# OpenBook.net
KiCad netlist of a schematic drawn in EAGLE
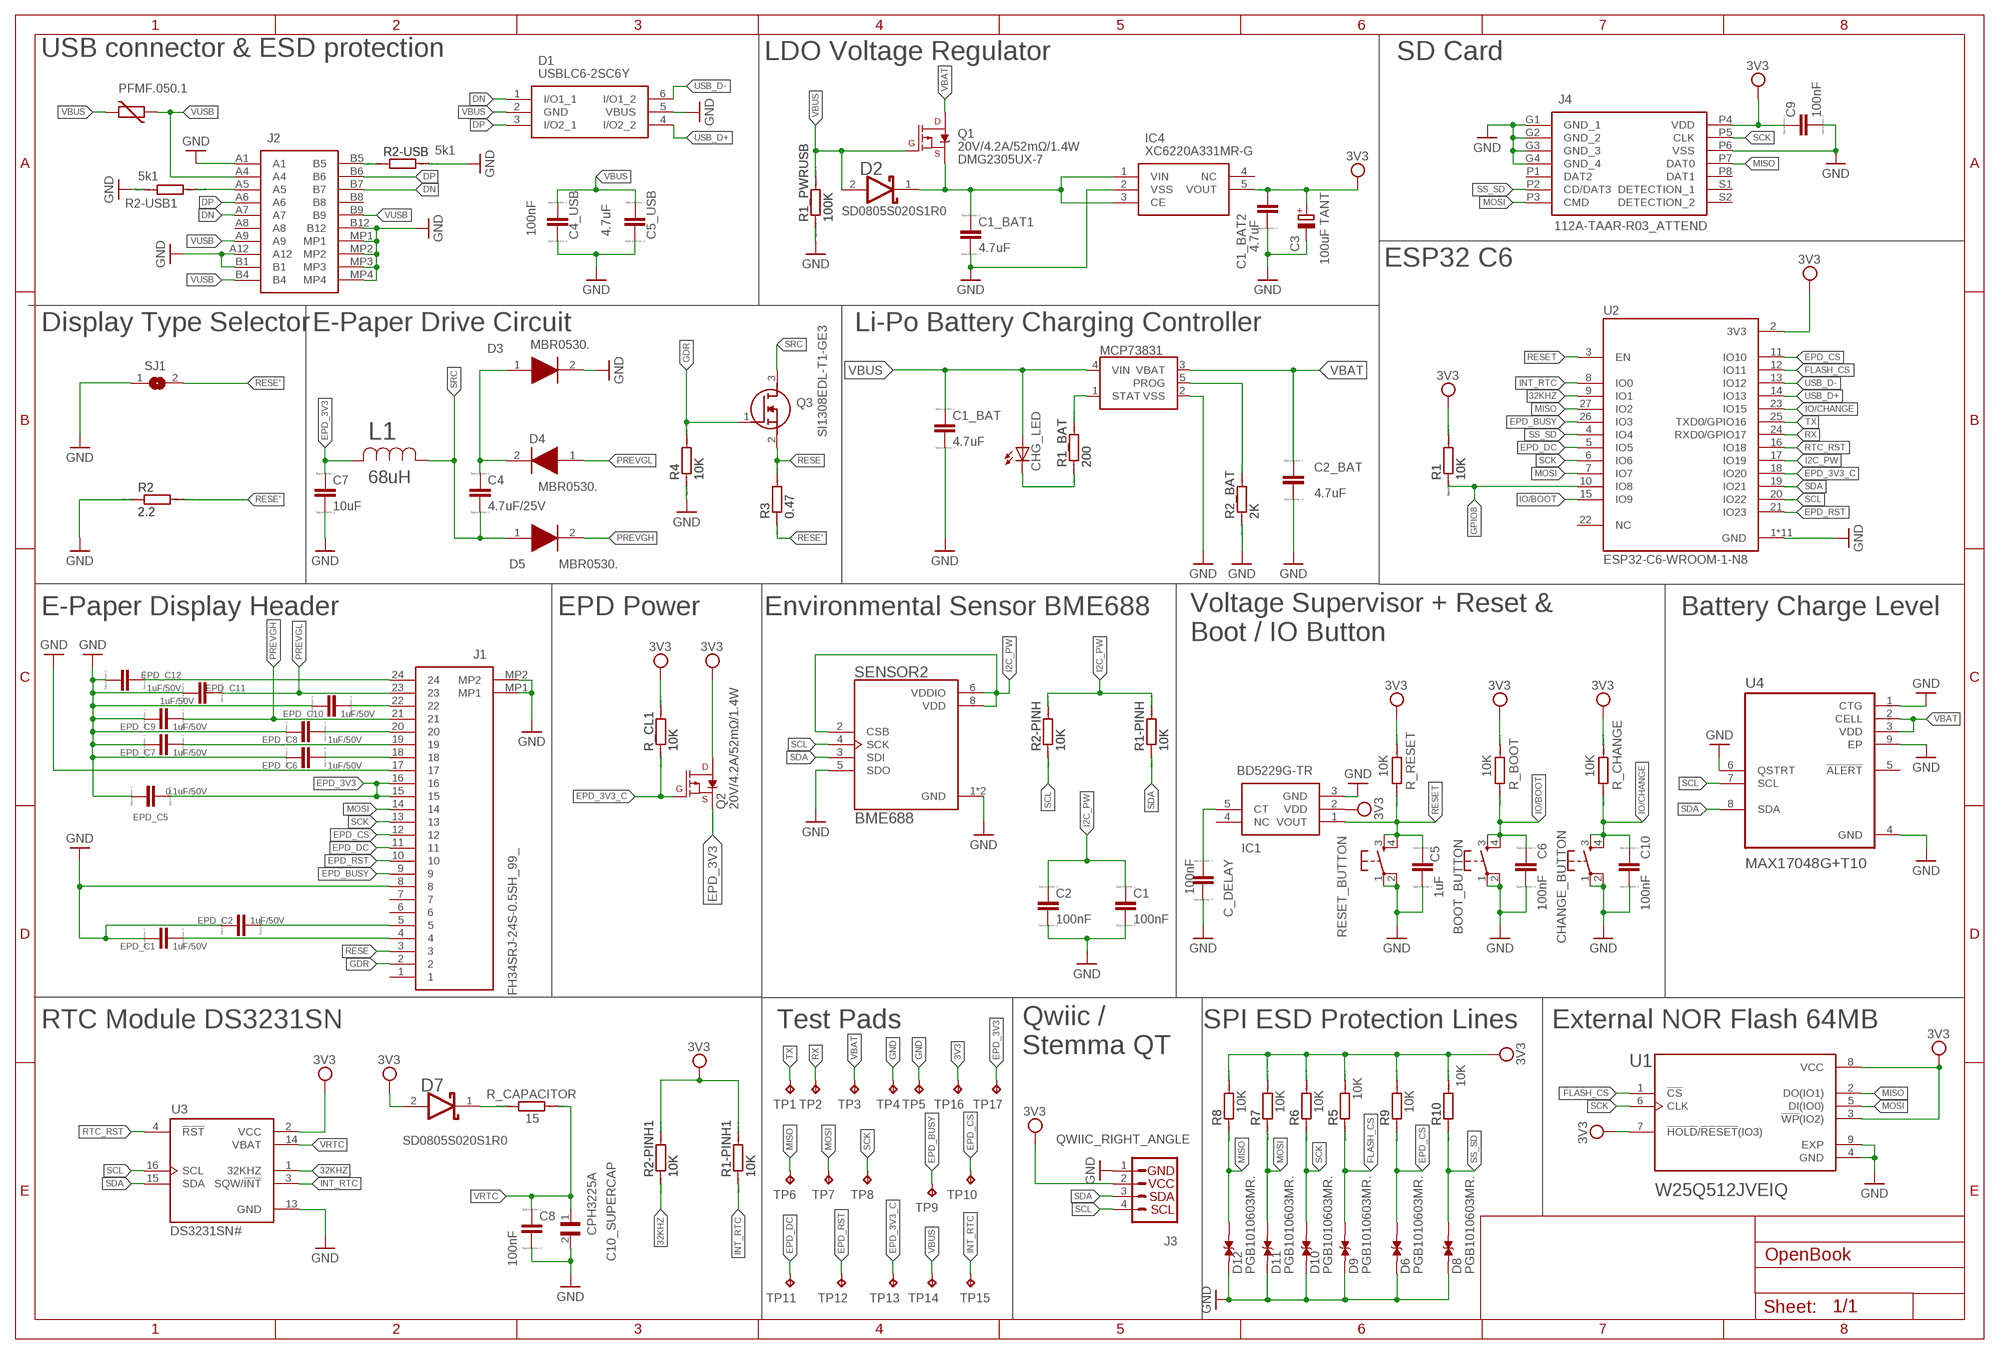
[diagram p0: schematic, sheet 1]

(export (version "E")
  (design (tool "Eeschema 10.0.6"))
  (components
    (comp (ref "BOOT_BUTTON")
      (value "BUTTON_CUSYOMV1V2")
      (footprint "eagle-import:MYBUTTON")
      (libsource (lib "eagle-import") (part "BUTTON_CUSYOMV1V2"))
    )
    (comp (ref "C1")
      (value "100nF")
      (footprint "eagle-import:EAGLE-LTSPICE_C0402")
      (libsource (lib "eagle-import") (part "EAGLE-LTSPICE_C"))
    )
    (comp (ref "C1_BAT")
      (value "4.7uF")
      (footprint "eagle-import:EAGLE-LTSPICE_C0402")
      (libsource (lib "eagle-import") (part "EAGLE-LTSPICE_C"))
    )
    (comp (ref "C1_BAT1")
      (value "4.7uF")
      (footprint "eagle-import:EAGLE-LTSPICE_C0402")
      (libsource (lib "eagle-import") (part "EAGLE-LTSPICE_C"))
    )
    (comp (ref "C1_BAT2")
      (value "4.7uF")
      (footprint "eagle-import:EAGLE-LTSPICE_C0402")
      (libsource (lib "eagle-import") (part "EAGLE-LTSPICE_C"))
    )
    (comp (ref "C2")
      (value "100nF")
      (footprint "eagle-import:EAGLE-LTSPICE_C0402")
      (libsource (lib "eagle-import") (part "EAGLE-LTSPICE_C"))
    )
    (comp (ref "C2_BAT")
      (value "4.7uF")
      (footprint "eagle-import:EAGLE-LTSPICE_C0402")
      (libsource (lib "eagle-import") (part "EAGLE-LTSPICE_C"))
    )
    (comp (ref "C3")
      (value "100uF TANT")
      (footprint "eagle-import:RCL_CT3528")
      (libsource (lib "eagle-import") (part "RCL_CPOL-EUCT3528"))
    )
    (comp (ref "C4")
      (value "4.7uF/25V")
      (footprint "eagle-import:EAGLE-LTSPICE_C0402")
      (libsource (lib "eagle-import") (part "EAGLE-LTSPICE_C"))
    )
    (comp (ref "C4_USB")
      (value "100nF")
      (footprint "eagle-import:EAGLE-LTSPICE_C0402")
      (libsource (lib "eagle-import") (part "EAGLE-LTSPICE_C"))
    )
    (comp (ref "C5")
      (value "1uF")
      (footprint "eagle-import:EAGLE-LTSPICE_C0402")
      (libsource (lib "eagle-import") (part "EAGLE-LTSPICE_C"))
    )
    (comp (ref "C5_USB")
      (value "4.7uF")
      (footprint "eagle-import:EAGLE-LTSPICE_C0402")
      (libsource (lib "eagle-import") (part "EAGLE-LTSPICE_C"))
    )
    (comp (ref "C6")
      (value "100nF")
      (footprint "eagle-import:EAGLE-LTSPICE_C0402")
      (libsource (lib "eagle-import") (part "EAGLE-LTSPICE_C"))
    )
    (comp (ref "C7")
      (value "10uF")
      (footprint "eagle-import:EAGLE-LTSPICE_C0402")
      (libsource (lib "eagle-import") (part "EAGLE-LTSPICE_C"))
    )
    (comp (ref "C8")
      (value "100nF")
      (footprint "eagle-import:EAGLE-LTSPICE_C0402")
      (libsource (lib "eagle-import") (part "EAGLE-LTSPICE_C"))
    )
    (comp (ref "C9")
      (value "100nF")
      (footprint "eagle-import:EAGLE-LTSPICE_C0402")
      (libsource (lib "eagle-import") (part "EAGLE-LTSPICE_C"))
    )
    (comp (ref "C10")
      (value "100nF")
      (footprint "eagle-import:EAGLE-LTSPICE_C0402")
      (libsource (lib "eagle-import") (part "EAGLE-LTSPICE_C"))
    )
    (comp (ref "C10_SUPERCAP")
      (value "CPH3225A")
      (footprint "eagle-import:CAPCP3225X100N")
      (fields (field (name "MF") "Seiko Instruments"))
      (libsource (lib "eagle-import") (part "CPH3225A"))
    )
    (comp (ref "CHANGE_BUTTON")
      (value "BUTTON_CUSYOMV1V2")
      (footprint "eagle-import:MYBUTTON")
      (libsource (lib "eagle-import") (part "BUTTON_CUSYOMV1V2"))
    )
    (comp (ref "CHG_LED")
      (value "ADAFRUIT_LEDCHIP-LED0603")
      (footprint "eagle-import:ADAFRUIT_CHIP-LED0603")
      (libsource (lib "eagle-import") (part "ADAFRUIT_LEDCHIP-LED0603"))
    )
    (comp (ref "C_DELAY")
      (value "100nF")
      (footprint "eagle-import:EAGLE-LTSPICE_C0402")
      (libsource (lib "eagle-import") (part "EAGLE-LTSPICE_C"))
    )
    (comp (ref "D1")
      (value "USBLC6-2SC6Y")
      (footprint "eagle-import:SOT95P280X145-6N")
      (fields (field (name "MF") "STMicroelectronics"))
      (libsource (lib "eagle-import") (part "USBLC6-2SC6Y"))
    )
    (comp (ref "D2")
      (value "SD0805S020S1R0")
      (footprint "eagle-import:ESP32_WROVER_AVX---SD0805S020S1R0_AVX_SD0805S020S1R0_0")
      (fields
        (field (name "DIGIKEY_PART_NUMBER") "478-7800-1-ND")
        (field (name "MF") "AVX")
        (field (name "MOUSER_PART_NUMBER") "581-SD0805S020S1R0")
      )
      (libsource (lib "eagle-import") (part "ESP32_WROVER_AVX---SD0805S020S1R0_AVX_SD0805S020S1R0_0_0AVX_SD0805S020S1R0_0_0"))
    )
    (comp (ref "D3")
      (value "MBR0530.")
      (footprint "eagle-import:SOD3716X135N")
      (libsource (lib "eagle-import") (part "MBR0530."))
    )
    (comp (ref "D4")
      (value "MBR0530.")
      (footprint "eagle-import:SOD3716X135N")
      (libsource (lib "eagle-import") (part "MBR0530."))
    )
    (comp (ref "D5")
      (value "MBR0530.")
      (footprint "eagle-import:SOD3716X135N")
      (libsource (lib "eagle-import") (part "MBR0530."))
    )
    (comp (ref "D6")
      (value "PGB1010603MR.")
      (footprint "eagle-import:DIOC1608X36N")
      (libsource (lib "eagle-import") (part "PGB1010603MR."))
    )
    (comp (ref "D7")
      (value "SD0805S020S1R0")
      (footprint "eagle-import:ESP32_WROVER_AVX---SD0805S020S1R0_AVX_SD0805S020S1R0_0")
      (fields
        (field (name "DIGIKEY_PART_NUMBER") "478-7800-1-ND")
        (field (name "MF") "AVX")
        (field (name "MOUSER_PART_NUMBER") "581-SD0805S020S1R0")
      )
      (libsource (lib "eagle-import") (part "ESP32_WROVER_AVX---SD0805S020S1R0_AVX_SD0805S020S1R0_0_0AVX_SD0805S020S1R0_0_0"))
    )
    (comp (ref "D8")
      (value "PGB1010603MR.")
      (footprint "eagle-import:DIOC1608X36N")
      (libsource (lib "eagle-import") (part "PGB1010603MR."))
    )
    (comp (ref "D9")
      (value "PGB1010603MR.")
      (footprint "eagle-import:DIOC1608X36N")
      (libsource (lib "eagle-import") (part "PGB1010603MR."))
    )
    (comp (ref "D10")
      (value "PGB1010603MR.")
      (footprint "eagle-import:DIOC1608X36N")
      (libsource (lib "eagle-import") (part "PGB1010603MR."))
    )
    (comp (ref "D11")
      (value "PGB1010603MR.")
      (footprint "eagle-import:DIOC1608X36N")
      (libsource (lib "eagle-import") (part "PGB1010603MR."))
    )
    (comp (ref "D12")
      (value "PGB1010603MR.")
      (footprint "eagle-import:DIOC1608X36N")
      (libsource (lib "eagle-import") (part "PGB1010603MR."))
    )
    (comp (ref "EPD_C1")
      (value "1uF/50V")
      (footprint "eagle-import:EAGLE-LTSPICE_C0402")
      (libsource (lib "eagle-import") (part "EAGLE-LTSPICE_C"))
    )
    (comp (ref "EPD_C2")
      (value "1uF/50V")
      (footprint "eagle-import:EAGLE-LTSPICE_C0402")
      (libsource (lib "eagle-import") (part "EAGLE-LTSPICE_C"))
    )
    (comp (ref "EPD_C5")
      (value "0.1uF/50V")
      (footprint "eagle-import:EAGLE-LTSPICE_C0402")
      (libsource (lib "eagle-import") (part "EAGLE-LTSPICE_C"))
    )
    (comp (ref "EPD_C6")
      (value "1uF/50V")
      (footprint "eagle-import:EAGLE-LTSPICE_C0402")
      (libsource (lib "eagle-import") (part "EAGLE-LTSPICE_C"))
    )
    (comp (ref "EPD_C7")
      (value "1uF/50V")
      (footprint "eagle-import:EAGLE-LTSPICE_C0402")
      (libsource (lib "eagle-import") (part "EAGLE-LTSPICE_C"))
    )
    (comp (ref "EPD_C8")
      (value "1uF/50V")
      (footprint "eagle-import:EAGLE-LTSPICE_C0402")
      (libsource (lib "eagle-import") (part "EAGLE-LTSPICE_C"))
    )
    (comp (ref "EPD_C9")
      (value "1uF/50V")
      (footprint "eagle-import:EAGLE-LTSPICE_C0402")
      (libsource (lib "eagle-import") (part "EAGLE-LTSPICE_C"))
    )
    (comp (ref "EPD_C10")
      (value "1uF/50V")
      (footprint "eagle-import:EAGLE-LTSPICE_C0402")
      (libsource (lib "eagle-import") (part "EAGLE-LTSPICE_C"))
    )
    (comp (ref "EPD_C11")
      (value "1uF/50V")
      (footprint "eagle-import:EAGLE-LTSPICE_C0402")
      (libsource (lib "eagle-import") (part "EAGLE-LTSPICE_C"))
    )
    (comp (ref "EPD_C12")
      (value "1uF/50V")
      (footprint "eagle-import:EAGLE-LTSPICE_C0402")
      (libsource (lib "eagle-import") (part "EAGLE-LTSPICE_C"))
    )
    (comp (ref "IC1")
      (value "BD5229G-TR")
      (footprint "eagle-import:SOT95P280X125-5N")
      (fields (field (name "MOUSER_PART_NUMBER") "755-BD5229G-TR"))
      (libsource (lib "eagle-import") (part "BD5229G-TR"))
    )
    (comp (ref "IC4")
      (value "XC6220A331MR-G")
      (footprint "eagle-import:SOT95P280X120-5N")
      (fields (field (name "MOUSER_PART_NUMBER") "865-XC6220A331MR-G"))
      (libsource (lib "eagle-import") (part "XC6220A331MR-G"))
    )
    (comp (ref "J1")
      (value "FH34SRJ-24S-0.5SH_99_")
      (footprint "eagle-import:FH34SRJ24S05SH99")
      (fields
        (field (name "MANUFACTURER_PART_NUMBER") "FH34SRJ-24S-0.5SH(99)")
        (field (name "MOUSER_PART_NUMBER") "798-FH34SRJ24S05SH99")
      )
      (libsource (lib "eagle-import") (part "FH34SRJ-24S-0.5SH_99_"))
    )
    (comp (ref "J2")
      (value "SAMACSYS_PARTS_USB4110-GF-A")
      (footprint "eagle-import:SAMACSYS_PARTS_USB4110GFA")
      (fields
        (field (name "MANUFACTURER_PART_NUMBER") "USB4110-GF-A")
        (field (name "MOUSER_PART_NUMBER") "640-USB4110-GF-A")
      )
      (libsource (lib "eagle-import") (part "SAMACSYS_PARTS_USB4110-GF-A"))
    )
    (comp (ref "J3")
      (value "QWIIC_RIGHT_ANGLE")
      (footprint "eagle-import:JST04_1MM_RA")
      (libsource (lib "eagle-import") (part "QWIIC_CONNECTORJS-1MM"))
    )
    (comp (ref "J4")
      (value "112A-TAAR-R03_ATTEND")
      (footprint "eagle-import:112ATAARR03ATTEND")
      (fields (field (name "MANUFACTURER_PART_NUMBER") "112A-TAAR-R03 ATTEND"))
      (libsource (lib "eagle-import") (part "112A-TAAR-R03_ATTEND"))
    )
    (comp (ref "L1")
      (value "68uH")
      (footprint "eagle-import:IND_4828-WE-TPC_WRE")
      (fields
        (field (name "MANUFACTURER_PART_NUMBER") "744043680")
        (field (name "COPYRIGHT") "Copyright (C) 2024 Ultra Librarian. All rights reserved.")
      )
      (libsource (lib "eagle-import") (part "744043680IND_4828-WE-TPC_WRE"))
    )
    (comp (ref "MCP73831")
      (value "ESP32_WROVER_SPARKFUN-IC-POWER_MCP73831")
      (footprint "eagle-import:ESP32_WROVER_SPARKFUN-IC-POWER_SOT23-5")
      (libsource (lib "eagle-import") (part "ESP32_WROVER_SPARKFUN-IC-POWER_MCP73831"))
    )
    (comp (ref "PFMF.050.1")
      (value "ESP32C6_VARISTORCN1812")
      (footprint "eagle-import:ESP32C6_VARISTOR_CT_CN1812")
      (libsource (lib "eagle-import") (part "ESP32C6_VARISTORCN1812"))
    )
    (comp (ref "Q1")
      (value "20V/4.2A/52mΩ/1.4W")
      (footprint "eagle-import:ESP32_WROVER_SPARKFUN-DISCRETESEMI_SOT23-3")
      (libsource (lib "eagle-import") (part "ESP32_WROVER_SPARKFUN-DISCRETESEMI_MOSFET_PCH-DMG2305UX-7"))
    )
    (comp (ref "Q2")
      (value "20V/4.2A/52mΩ/1.4W")
      (footprint "eagle-import:ESP32_WROVER_SPARKFUN-DISCRETESEMI_SOT23-3")
      (libsource (lib "eagle-import") (part "ESP32_WROVER_SPARKFUN-DISCRETESEMI_MOSFET_PCH-DMG2305UX-7"))
    )
    (comp (ref "Q3")
      (value "SI1308EDL-T1-GE3")
      (footprint "eagle-import:SOT65P210X110-3N")
      (fields (field (name "MF") "Vishay Siliconix"))
      (libsource (lib "eagle-import") (part "SI1308EDL-T1-GE3"))
    )
    (comp (ref "R1")
      (value "10K")
      (footprint "eagle-import:ESP32_WROVER_EAGLE-LTSPICE_R0402")
      (libsource (lib "eagle-import") (part "ESP32_WROVER_EAGLE-LTSPICE_R"))
    )
    (comp (ref "R1-PINH")
      (value "10K")
      (footprint "eagle-import:ESP32_WROVER_EAGLE-LTSPICE_R0402")
      (libsource (lib "eagle-import") (part "ESP32_WROVER_EAGLE-LTSPICE_R"))
    )
    (comp (ref "R1-PINH1")
      (value "10K")
      (footprint "eagle-import:ESP32_WROVER_EAGLE-LTSPICE_R0402")
      (libsource (lib "eagle-import") (part "ESP32_WROVER_EAGLE-LTSPICE_R"))
    )
    (comp (ref "R1_BAT")
      (value "200")
      (footprint "eagle-import:ESP32_WROVER_EAGLE-LTSPICE_R0402")
      (libsource (lib "eagle-import") (part "ESP32_WROVER_EAGLE-LTSPICE_R"))
    )
    (comp (ref "R1_PWRUSB")
      (value "100K")
      (footprint "eagle-import:ESP32_WROVER_EAGLE-LTSPICE_R0402")
      (libsource (lib "eagle-import") (part "ESP32_WROVER_EAGLE-LTSPICE_R"))
    )
    (comp (ref "R2")
      (value "2.2")
      (footprint "eagle-import:ESP32_WROVER_EAGLE-LTSPICE_R0402")
      (libsource (lib "eagle-import") (part "ESP32_WROVER_EAGLE-LTSPICE_R"))
    )
    (comp (ref "R2-PINH")
      (value "10K")
      (footprint "eagle-import:ESP32_WROVER_EAGLE-LTSPICE_R0402")
      (libsource (lib "eagle-import") (part "ESP32_WROVER_EAGLE-LTSPICE_R"))
    )
    (comp (ref "R2-PINH1")
      (value "10K")
      (footprint "eagle-import:ESP32_WROVER_EAGLE-LTSPICE_R0402")
      (libsource (lib "eagle-import") (part "ESP32_WROVER_EAGLE-LTSPICE_R"))
    )
    (comp (ref "R2-USB")
      (value "5k1")
      (footprint "eagle-import:ESP32_WROVER_EAGLE-LTSPICE_R0402")
      (libsource (lib "eagle-import") (part "ESP32_WROVER_EAGLE-LTSPICE_R"))
    )
    (comp (ref "R2-USB1")
      (value "5k1")
      (footprint "eagle-import:ESP32_WROVER_EAGLE-LTSPICE_R0402")
      (libsource (lib "eagle-import") (part "ESP32_WROVER_EAGLE-LTSPICE_R"))
    )
    (comp (ref "R2_BAT")
      (value "2K")
      (footprint "eagle-import:ESP32_WROVER_EAGLE-LTSPICE_R0402")
      (libsource (lib "eagle-import") (part "ESP32_WROVER_EAGLE-LTSPICE_R"))
    )
    (comp (ref "R3")
      (value "0.47")
      (footprint "eagle-import:ESP32_WROVER_EAGLE-LTSPICE_R0402")
      (libsource (lib "eagle-import") (part "ESP32_WROVER_EAGLE-LTSPICE_R"))
    )
    (comp (ref "R4")
      (value "10K")
      (footprint "eagle-import:ESP32_WROVER_EAGLE-LTSPICE_R0402")
      (libsource (lib "eagle-import") (part "ESP32_WROVER_EAGLE-LTSPICE_R"))
    )
    (comp (ref "R5")
      (value "10K")
      (footprint "eagle-import:ESP32_WROVER_EAGLE-LTSPICE_R0402")
      (libsource (lib "eagle-import") (part "ESP32_WROVER_EAGLE-LTSPICE_R"))
    )
    (comp (ref "R6")
      (value "10K")
      (footprint "eagle-import:ESP32_WROVER_EAGLE-LTSPICE_R0402")
      (libsource (lib "eagle-import") (part "ESP32_WROVER_EAGLE-LTSPICE_R"))
    )
    (comp (ref "R7")
      (value "10K")
      (footprint "eagle-import:ESP32_WROVER_EAGLE-LTSPICE_R0402")
      (libsource (lib "eagle-import") (part "ESP32_WROVER_EAGLE-LTSPICE_R"))
    )
    (comp (ref "R8")
      (value "10K")
      (footprint "eagle-import:ESP32_WROVER_EAGLE-LTSPICE_R0402")
      (libsource (lib "eagle-import") (part "ESP32_WROVER_EAGLE-LTSPICE_R"))
    )
    (comp (ref "R9")
      (value "10K")
      (footprint "eagle-import:ESP32_WROVER_EAGLE-LTSPICE_R0402")
      (libsource (lib "eagle-import") (part "ESP32_WROVER_EAGLE-LTSPICE_R"))
    )
    (comp (ref "R10")
      (value "10K")
      (footprint "eagle-import:ESP32_WROVER_EAGLE-LTSPICE_R0402")
      (libsource (lib "eagle-import") (part "ESP32_WROVER_EAGLE-LTSPICE_R"))
    )
    (comp (ref "RESET_BUTTON")
      (value "BUTTON_CUSYOMV1V2")
      (footprint "eagle-import:MYBUTTON")
      (libsource (lib "eagle-import") (part "BUTTON_CUSYOMV1V2"))
    )
    (comp (ref "R_BOOT")
      (value "10K")
      (footprint "eagle-import:ESP32_WROVER_EAGLE-LTSPICE_R0402")
      (libsource (lib "eagle-import") (part "ESP32_WROVER_EAGLE-LTSPICE_R"))
    )
    (comp (ref "R_CAPACITOR")
      (value "15")
      (footprint "eagle-import:ESP32_WROVER_EAGLE-LTSPICE_R0402")
      (libsource (lib "eagle-import") (part "ESP32_WROVER_EAGLE-LTSPICE_R"))
    )
    (comp (ref "R_CHANGE")
      (value "10K")
      (footprint "eagle-import:ESP32_WROVER_EAGLE-LTSPICE_R0402")
      (libsource (lib "eagle-import") (part "ESP32_WROVER_EAGLE-LTSPICE_R"))
    )
    (comp (ref "R_CL1")
      (value "10K")
      (footprint "eagle-import:ESP32_WROVER_EAGLE-LTSPICE_R0402")
      (libsource (lib "eagle-import") (part "ESP32_WROVER_EAGLE-LTSPICE_R"))
    )
    (comp (ref "R_RESET")
      (value "10K")
      (footprint "eagle-import:ESP32_WROVER_EAGLE-LTSPICE_R0402")
      (libsource (lib "eagle-import") (part "ESP32_WROVER_EAGLE-LTSPICE_R"))
    )
    (comp (ref "SENSOR2")
      (value "BME688")
      (footprint "eagle-import:ESP32_WROVER_BME680_PSON80P300X300X100-8N")
      (fields (field (name "MF") "Bosch Sensortec") (field (name "MP") "BME680"))
      (libsource (lib "eagle-import") (part "ESP32_WROVER_BME680_BME680"))
    )
    (comp (ref "SJ1") (value "SJ") (footprint "eagle-import:SJ") (libsource (lib "eagle-import") (part "SJ")))
    (comp (ref "TP1")
      (value "TPV1")
      (footprint "eagle-import:TP20R")
      (libsource (lib "eagle-import") (part "TPV1"))
    )
    (comp (ref "TP2")
      (value "TPV1")
      (footprint "eagle-import:TP20R")
      (libsource (lib "eagle-import") (part "TPV1"))
    )
    (comp (ref "TP3")
      (value "TPV1")
      (footprint "eagle-import:TP20R")
      (libsource (lib "eagle-import") (part "TPV1"))
    )
    (comp (ref "TP4")
      (value "TPV1")
      (footprint "eagle-import:TP20R")
      (libsource (lib "eagle-import") (part "TPV1"))
    )
    (comp (ref "TP5")
      (value "TPV1")
      (footprint "eagle-import:TP20R")
      (libsource (lib "eagle-import") (part "TPV1"))
    )
    (comp (ref "TP6")
      (value "TPV1")
      (footprint "eagle-import:TP20R")
      (libsource (lib "eagle-import") (part "TPV1"))
    )
    (comp (ref "TP7")
      (value "TPV1")
      (footprint "eagle-import:TP20R")
      (libsource (lib "eagle-import") (part "TPV1"))
    )
    (comp (ref "TP8")
      (value "TPV1")
      (footprint "eagle-import:TP20R")
      (libsource (lib "eagle-import") (part "TPV1"))
    )
    (comp (ref "TP9")
      (value "TPV1")
      (footprint "eagle-import:TP20R")
      (libsource (lib "eagle-import") (part "TPV1"))
    )
    (comp (ref "TP10")
      (value "TPV1")
      (footprint "eagle-import:TP20R")
      (libsource (lib "eagle-import") (part "TPV1"))
    )
    (comp (ref "TP11")
      (value "TPV1")
      (footprint "eagle-import:TP20R")
      (libsource (lib "eagle-import") (part "TPV1"))
    )
    (comp (ref "TP12")
      (value "TPV1")
      (footprint "eagle-import:TP20R")
      (libsource (lib "eagle-import") (part "TPV1"))
    )
    (comp (ref "TP13")
      (value "TPV1")
      (footprint "eagle-import:TP20R")
      (libsource (lib "eagle-import") (part "TPV1"))
    )
    (comp (ref "TP14")
      (value "TPV1")
      (footprint "eagle-import:TP20R")
      (libsource (lib "eagle-import") (part "TPV1"))
    )
    (comp (ref "TP15")
      (value "TPV1")
      (footprint "eagle-import:TP20R")
      (libsource (lib "eagle-import") (part "TPV1"))
    )
    (comp (ref "TP16")
      (value "TPV1")
      (footprint "eagle-import:TP20R")
      (libsource (lib "eagle-import") (part "TPV1"))
    )
    (comp (ref "TP17")
      (value "TPV1")
      (footprint "eagle-import:TP20R")
      (libsource (lib "eagle-import") (part "TPV1"))
    )
    (comp (ref "U1")
      (value "W25Q512JVEIQ")
      (footprint "eagle-import:SON127P600X800X80-9N")
      (fields (field (name "MF") "Winbond Electronics"))
      (libsource (lib "eagle-import") (part "W25Q512JVEIQ"))
    )
    (comp (ref "U2")
      (value "ESP32-C6-WROOM-1-N8")
      (footprint "eagle-import:XCVR_ESP32-C6-WROOM-1-N8")
      (fields (field (name "MF") "Espressif Systems"))
      (libsource (lib "eagle-import") (part "ESP32-C6-WROOM-1-N8"))
    )
    (comp (ref "U3")
      (value "DS3231SN#")
      (footprint "eagle-import:SOIC127P1032X265-16N")
      (fields (field (name "MF") "Analog Devices"))
      (libsource (lib "eagle-import") (part "DS3231SN#"))
    )
    (comp (ref "U4")
      (value "MAX17048G+T10")
      (footprint "eagle-import:SON50P200X200X80-9N")
      (fields (field (name "MF") "Analog Devices"))
      (libsource (lib "eagle-import") (part "MAX17048G+T10"))
    )
  )
  (nets
    (net (code "1") (name "3V3") (class "Default")
      (node (ref "C1_BAT2") (pin "1") (pinfunction "1_1") (pintype "passive"))
      (node (ref "C3") (pin "+") (pinfunction "+_+") (pintype "passive"))
      (node (ref "C9") (pin "1") (pinfunction "1_1") (pintype "passive"))
      (node (ref "D7") (pin "2") (pinfunction "ANODE_2") (pintype "bidirectional"))
      (node (ref "IC1") (pin "2") (pinfunction "VDD_2") (pintype "bidirectional"))
      (node (ref "IC4") (pin "5") (pinfunction "VOUT_5") (pintype "bidirectional"))
      (node (ref "J3") (pin "2") (pinfunction "2_2") (pintype "power_in"))
      (node (ref "J4") (pin "P4") (pinfunction "VDD_P4") (pintype "bidirectional"))
      (node (ref "Q2") (pin "3") (pinfunction "D_3") (pintype "bidirectional"))
      (node (ref "R1") (pin "2") (pinfunction "2_2") (pintype "passive"))
      (node (ref "R1-PINH1") (pin "2") (pinfunction "2_2") (pintype "passive"))
      (node (ref "R10") (pin "2") (pinfunction "2_2") (pintype "passive"))
      (node (ref "R2-PINH1") (pin "2") (pinfunction "2_2") (pintype "passive"))
      (node (ref "R5") (pin "2") (pinfunction "2_2") (pintype "passive"))
      (node (ref "R6") (pin "2") (pinfunction "2_2") (pintype "passive"))
      (node (ref "R7") (pin "2") (pinfunction "2_2") (pintype "passive"))
      (node (ref "R8") (pin "2") (pinfunction "2_2") (pintype "passive"))
      (node (ref "R9") (pin "2") (pinfunction "2_2") (pintype "passive"))
      (node (ref "R_BOOT") (pin "2") (pinfunction "2_2") (pintype "passive"))
      (node (ref "R_CHANGE") (pin "2") (pinfunction "2_2") (pintype "passive"))
      (node (ref "R_CL1") (pin "2") (pinfunction "2_2") (pintype "passive"))
      (node (ref "R_RESET") (pin "2") (pinfunction "2_2") (pintype "passive"))
      (node (ref "TP16") (pin "TP") (pinfunction "TP_TP") (pintype "input"))
      (node (ref "U1") (pin "3") (pinfunction "~{WP}(IO2)_3") (pintype "bidirectional"))
      (node (ref "U1") (pin "7") (pinfunction "~{HOLD}/~{RESET}(IO3)_7") (pintype "bidirectional"))
      (node (ref "U1") (pin "8") (pinfunction "VCC_8") (pintype "power_in"))
      (node (ref "U2") (pin "2") (pinfunction "3V3_2") (pintype "power_in"))
      (node (ref "U3") (pin "2") (pinfunction "VCC_2") (pintype "power_in"))
    )
    (net (code "2") (name "32KHZ") (class "Default")
      (node (ref "R2-PINH1") (pin "1") (pinfunction "1_1") (pintype "passive"))
      (node (ref "U2") (pin "9") (pinfunction "IO1_9") (pintype "bidirectional"))
      (node (ref "U3") (pin "1") (pinfunction "32KHZ_1") (pintype "output"))
    )
    (net (code "3") (name "DN") (class "Default")
      (node (ref "D1") (pin "1") (pinfunction "I/O1_1_1") (pintype "bidirectional"))
      (node (ref "J2") (pin "A7") (pinfunction "A7_A7") (pintype "bidirectional"))
      (node (ref "J2") (pin "B7") (pinfunction "B7_B7") (pintype "bidirectional"))
    )
    (net (code "4") (name "DP") (class "Default")
      (node (ref "D1") (pin "3") (pinfunction "I/O2_1_3") (pintype "bidirectional"))
      (node (ref "J2") (pin "A6") (pinfunction "A6_A6") (pintype "bidirectional"))
      (node (ref "J2") (pin "B6") (pinfunction "B6_B6") (pintype "bidirectional"))
    )
    (net (code "5") (name "EPD_3V3") (class "Default")
      (node (ref "C7") (pin "1") (pinfunction "1_1") (pintype "passive"))
      (node (ref "EPD_C5") (pin "2") (pinfunction "2_2") (pintype "passive"))
      (node (ref "J1") (pin "15") (pinfunction "15_15") (pintype "bidirectional"))
      (node (ref "J1") (pin "16") (pinfunction "16_16") (pintype "bidirectional"))
      (node (ref "L1") (pin "2") (pinfunction "2_2") (pintype "passive"))
      (node (ref "Q2") (pin "2") (pinfunction "S_2") (pintype "bidirectional"))
      (node (ref "TP17") (pin "TP") (pinfunction "TP_TP") (pintype "input"))
    )
    (net (code "6") (name "EPD_3V3_C") (class "Default")
      (node (ref "Q2") (pin "1") (pinfunction "G_1") (pintype "bidirectional"))
      (node (ref "R_CL1") (pin "1") (pinfunction "1_1") (pintype "passive"))
      (node (ref "TP13") (pin "TP") (pinfunction "TP_TP") (pintype "input"))
      (node (ref "U2") (pin "18") (pinfunction "IO20_18") (pintype "bidirectional"))
    )
    (net (code "7") (name "EPD_BUSY") (class "Default")
      (node (ref "J1") (pin "9") (pinfunction "9_9") (pintype "bidirectional"))
      (node (ref "TP9") (pin "TP") (pinfunction "TP_TP") (pintype "input"))
      (node (ref "U2") (pin "26") (pinfunction "IO3_26") (pintype "bidirectional"))
    )
    (net (code "8") (name "EPD_CS") (class "Default")
      (node (ref "D6") (pin "2") (pinfunction "2_2") (pintype "passive"))
      (node (ref "J1") (pin "12") (pinfunction "12_12") (pintype "bidirectional"))
      (node (ref "R9") (pin "1") (pinfunction "1_1") (pintype "passive"))
      (node (ref "TP10") (pin "TP") (pinfunction "TP_TP") (pintype "input"))
      (node (ref "U2") (pin "11") (pinfunction "IO10_11") (pintype "bidirectional"))
    )
    (net (code "9") (name "EPD_DC") (class "Default")
      (node (ref "J1") (pin "11") (pinfunction "11_11") (pintype "bidirectional"))
      (node (ref "TP11") (pin "TP") (pinfunction "TP_TP") (pintype "input"))
      (node (ref "U2") (pin "5") (pinfunction "IO5_5") (pintype "bidirectional"))
    )
    (net (code "10") (name "EPD_RST") (class "Default")
      (node (ref "J1") (pin "10") (pinfunction "10_10") (pintype "bidirectional"))
      (node (ref "TP12") (pin "TP") (pinfunction "TP_TP") (pintype "input"))
      (node (ref "U2") (pin "21") (pinfunction "IO23_21") (pintype "bidirectional"))
    )
    (net (code "11") (name "FLASH_CS") (class "Default")
      (node (ref "D9") (pin "2") (pinfunction "2_2") (pintype "passive"))
      (node (ref "R5") (pin "1") (pinfunction "1_1") (pintype "passive"))
      (node (ref "U1") (pin "1") (pinfunction "~{CS}_1") (pintype "input"))
      (node (ref "U2") (pin "12") (pinfunction "IO11_12") (pintype "bidirectional"))
    )
    (net (code "12") (name "GDR") (class "Default")
      (node (ref "J1") (pin "2") (pinfunction "2_2") (pintype "bidirectional"))
      (node (ref "Q3") (pin "1") (pinfunction "G_1") (pintype "bidirectional"))
      (node (ref "R4") (pin "2") (pinfunction "2_2") (pintype "passive"))
    )
    (net (code "13") (name "GND") (class "Default")
      (node (ref "BOOT_BUTTON") (pin "1") (pinfunction "1_1") (pintype "passive"))
      (node (ref "BOOT_BUTTON") (pin "2") (pinfunction "2_2") (pintype "passive"))
      (node (ref "C1") (pin "2") (pinfunction "2_2") (pintype "passive"))
      (node (ref "C10") (pin "2") (pinfunction "2_2") (pintype "passive"))
      (node (ref "C10_SUPERCAP") (pin "2") (pinfunction "2_2") (pintype "passive"))
      (node (ref "C1_BAT") (pin "2") (pinfunction "2_2") (pintype "passive"))
      (node (ref "C1_BAT1") (pin "2") (pinfunction "2_2") (pintype "passive"))
      (node (ref "C1_BAT2") (pin "2") (pinfunction "2_2") (pintype "passive"))
      (node (ref "C2") (pin "2") (pinfunction "2_2") (pintype "passive"))
      (node (ref "C2_BAT") (pin "2") (pinfunction "2_2") (pintype "passive"))
      (node (ref "C3") (pin "-") (pinfunction "-_-") (pintype "passive"))
      (node (ref "C4_USB") (pin "2") (pinfunction "2_2") (pintype "passive"))
      (node (ref "C5") (pin "2") (pinfunction "2_2") (pintype "passive"))
      (node (ref "C5_USB") (pin "2") (pinfunction "2_2") (pintype "passive"))
      (node (ref "C6") (pin "2") (pinfunction "2_2") (pintype "passive"))
      (node (ref "C7") (pin "2") (pinfunction "2_2") (pintype "passive"))
      (node (ref "C8") (pin "2") (pinfunction "2_2") (pintype "passive"))
      (node (ref "C9") (pin "2") (pinfunction "2_2") (pintype "passive"))
      (node (ref "CHANGE_BUTTON") (pin "1") (pinfunction "1_1") (pintype "passive"))
      (node (ref "CHANGE_BUTTON") (pin "2") (pinfunction "2_2") (pintype "passive"))
      (node (ref "C_DELAY") (pin "2") (pinfunction "2_2") (pintype "passive"))
      (node (ref "D1") (pin "5") (pinfunction "VBUS_5") (pintype "bidirectional"))
      (node (ref "D10") (pin "1") (pinfunction "1_1") (pintype "passive"))
      (node (ref "D11") (pin "1") (pinfunction "1_1") (pintype "passive"))
      (node (ref "D12") (pin "1") (pinfunction "1_1") (pintype "passive"))
      (node (ref "D3") (pin "2") (pinfunction "K_2") (pintype "bidirectional"))
      (node (ref "D6") (pin "1") (pinfunction "1_1") (pintype "passive"))
      (node (ref "D8") (pin "1") (pinfunction "1_1") (pintype "passive"))
      (node (ref "D9") (pin "1") (pinfunction "1_1") (pintype "passive"))
      (node (ref "EPD_C1") (pin "1") (pinfunction "1_1") (pintype "passive"))
      (node (ref "EPD_C10") (pin "1") (pinfunction "1_1") (pintype "passive"))
      (node (ref "EPD_C11") (pin "1") (pinfunction "1_1") (pintype "passive"))
      (node (ref "EPD_C12") (pin "1") (pinfunction "1_1") (pintype "passive"))
      (node (ref "EPD_C2") (pin "1") (pinfunction "1_1") (pintype "passive"))
      (node (ref "EPD_C5") (pin "1") (pinfunction "1_1") (pintype "passive"))
      (node (ref "EPD_C6") (pin "1") (pinfunction "1_1") (pintype "passive"))
      (node (ref "EPD_C7") (pin "1") (pinfunction "1_1") (pintype "passive"))
      (node (ref "EPD_C8") (pin "1") (pinfunction "1_1") (pintype "passive"))
      (node (ref "EPD_C9") (pin "1") (pinfunction "1_1") (pintype "passive"))
      (node (ref "IC1") (pin "3") (pinfunction "GND_3") (pintype "bidirectional"))
      (node (ref "IC4") (pin "2") (pinfunction "VSS_2") (pintype "bidirectional"))
      (node (ref "J1") (pin "17") (pinfunction "17_17") (pintype "bidirectional"))
      (node (ref "J1") (pin "8") (pinfunction "8_8") (pintype "bidirectional"))
      (node (ref "J1") (pin "MP1") (pinfunction "MP1_MP1") (pintype "bidirectional"))
      (node (ref "J1") (pin "MP2") (pinfunction "MP2_MP2") (pintype "bidirectional"))
      (node (ref "J2") (pin "A1") (pinfunction "A1_A1") (pintype "bidirectional"))
      (node (ref "J2") (pin "A12") (pinfunction "A12_A12") (pintype "bidirectional"))
      (node (ref "J2") (pin "B1") (pinfunction "B1_B1") (pintype "bidirectional"))
      (node (ref "J2") (pin "B12") (pinfunction "B12_B12") (pintype "bidirectional"))
      (node (ref "J2") (pin "MP1") (pinfunction "MP1_MP1") (pintype "bidirectional"))
      (node (ref "J2") (pin "MP2") (pinfunction "MP2_MP2") (pintype "bidirectional"))
      (node (ref "J2") (pin "MP3") (pinfunction "MP3_MP3") (pintype "bidirectional"))
      (node (ref "J2") (pin "MP4") (pinfunction "MP4_MP4") (pintype "bidirectional"))
      (node (ref "J3") (pin "1") (pinfunction "1_1") (pintype "power_in"))
      (node (ref "J4") (pin "G1") (pinfunction "GND_1_G1") (pintype "bidirectional"))
      (node (ref "J4") (pin "G2") (pinfunction "GND_2_G2") (pintype "bidirectional"))
      (node (ref "J4") (pin "G3") (pinfunction "GND_3_G3") (pintype "bidirectional"))
      (node (ref "J4") (pin "G4") (pinfunction "GND_4_G4") (pintype "bidirectional"))
      (node (ref "J4") (pin "P6") (pinfunction "VSS_P6") (pintype "bidirectional"))
      (node (ref "MCP73831") (pin "2") (pinfunction "VSS_2") (pintype "power_in"))
      (node (ref "R1_PWRUSB") (pin "1") (pinfunction "1_1") (pintype "passive"))
      (node (ref "R2") (pin "1") (pinfunction "1_1") (pintype "passive"))
      (node (ref "R2-USB") (pin "2") (pinfunction "2_2") (pintype "passive"))
      (node (ref "R2-USB1") (pin "1") (pinfunction "1_1") (pintype "passive"))
      (node (ref "R2_BAT") (pin "1") (pinfunction "1_1") (pintype "passive"))
      (node (ref "R4") (pin "1") (pinfunction "1_1") (pintype "passive"))
      (node (ref "RESET_BUTTON") (pin "1") (pinfunction "1_1") (pintype "passive"))
      (node (ref "RESET_BUTTON") (pin "2") (pinfunction "2_2") (pintype "passive"))
      (node (ref "SENSOR2") (pin "1") (pinfunction "GND_1") (pintype "power_in"))
      (node (ref "SENSOR2") (pin "5") (pinfunction "SDO_5") (pintype "bidirectional"))
      (node (ref "SENSOR2") (pin "7") (pinfunction "GND_7") (pintype "power_in"))
      (node (ref "SJ1") (pin "1") (pinfunction "1_1") (pintype "passive"))
      (node (ref "TP4") (pin "TP") (pinfunction "TP_TP") (pintype "input"))
      (node (ref "TP5") (pin "TP") (pinfunction "TP_TP") (pintype "input"))
      (node (ref "U1") (pin "4") (pinfunction "GND_4") (pintype "power_in"))
      (node (ref "U1") (pin "9") (pinfunction "EXP_9") (pintype "passive"))
      (node (ref "U2") (pin "1") (pinfunction "GND_1") (pintype "power_in"))
      (node (ref "U2") (pin "28") (pinfunction "GND_28") (pintype "power_in"))
      (node (ref "U2") (pin "29_1") (pinfunction "GND_29_1") (pintype "power_in"))
      (node (ref "U2") (pin "29_2") (pinfunction "GND_29_2") (pintype "power_in"))
      (node (ref "U2") (pin "29_3") (pinfunction "GND_29_3") (pintype "power_in"))
      (node (ref "U2") (pin "29_4") (pinfunction "GND_29_4") (pintype "power_in"))
      (node (ref "U2") (pin "29_5") (pinfunction "GND_29_5") (pintype "power_in"))
      (node (ref "U2") (pin "29_6") (pinfunction "GND_29_6") (pintype "power_in"))
      (node (ref "U2") (pin "29_7") (pinfunction "GND_29_7") (pintype "power_in"))
      (node (ref "U2") (pin "29_8") (pinfunction "GND_29_8") (pintype "power_in"))
      (node (ref "U2") (pin "29_9") (pinfunction "GND_29_9") (pintype "power_in"))
      (node (ref "U3") (pin "13") (pinfunction "GND_13") (pintype "power_in"))
      (node (ref "U4") (pin "1") (pinfunction "CTG_1") (pintype "power_in"))
      (node (ref "U4") (pin "4") (pinfunction "GND_4") (pintype "power_in"))
      (node (ref "U4") (pin "6") (pinfunction "QSTRT_6") (pintype "input"))
      (node (ref "U4") (pin "9") (pinfunction "EP_9") (pintype "power_in"))
    )
    (net (code "14") (name "GPIO8") (class "Default")
      (node (ref "R1") (pin "1") (pinfunction "1_1") (pintype "passive"))
      (node (ref "U2") (pin "10") (pinfunction "IO8_10") (pintype "bidirectional"))
    )
    (net (code "15") (name "I2C_PW") (class "Default")
      (node (ref "C1") (pin "1") (pinfunction "1_1") (pintype "passive"))
      (node (ref "C2") (pin "1") (pinfunction "1_1") (pintype "passive"))
      (node (ref "R1-PINH") (pin "2") (pinfunction "2_2") (pintype "passive"))
      (node (ref "R2-PINH") (pin "2") (pinfunction "2_2") (pintype "passive"))
      (node (ref "SENSOR2") (pin "2") (pinfunction "CSB_2") (pintype "input"))
      (node (ref "SENSOR2") (pin "6") (pinfunction "VDDIO_6") (pintype "power_in"))
      (node (ref "SENSOR2") (pin "8") (pinfunction "VDD_8") (pintype "power_in"))
      (node (ref "U2") (pin "17") (pinfunction "IO19_17") (pintype "bidirectional"))
    )
    (net (code "16") (name "INT_RTC") (class "Default")
      (node (ref "R1-PINH1") (pin "1") (pinfunction "1_1") (pintype "passive"))
      (node (ref "TP15") (pin "TP") (pinfunction "TP_TP") (pintype "input"))
      (node (ref "U2") (pin "8") (pinfunction "IO0_8") (pintype "bidirectional"))
      (node (ref "U3") (pin "3") (pinfunction "SQW/~{INT}_3") (pintype "output"))
    )
    (net (code "17") (name "IO{slash}BOOT") (class "Default")
      (node (ref "BOOT_BUTTON") (pin "3") (pinfunction "3_3") (pintype "passive"))
      (node (ref "BOOT_BUTTON") (pin "4") (pinfunction "4_4") (pintype "passive"))
      (node (ref "C6") (pin "1") (pinfunction "1_1") (pintype "passive"))
      (node (ref "R_BOOT") (pin "1") (pinfunction "1_1") (pintype "passive"))
      (node (ref "U2") (pin "15") (pinfunction "IO9_15") (pintype "bidirectional"))
    )
    (net (code "18") (name "IO{slash}CHANGE") (class "Default")
      (node (ref "C10") (pin "1") (pinfunction "1_1") (pintype "passive"))
      (node (ref "CHANGE_BUTTON") (pin "3") (pinfunction "3_3") (pintype "passive"))
      (node (ref "CHANGE_BUTTON") (pin "4") (pinfunction "4_4") (pintype "passive"))
      (node (ref "R_CHANGE") (pin "1") (pinfunction "1_1") (pintype "passive"))
      (node (ref "U2") (pin "23") (pinfunction "IO15_23") (pintype "bidirectional"))
    )
    (net (code "19") (name "MISO") (class "Default")
      (node (ref "D12") (pin "2") (pinfunction "2_2") (pintype "passive"))
      (node (ref "J4") (pin "P7") (pinfunction "DAT0_P7") (pintype "bidirectional"))
      (node (ref "R8") (pin "1") (pinfunction "1_1") (pintype "passive"))
      (node (ref "TP6") (pin "TP") (pinfunction "TP_TP") (pintype "input"))
      (node (ref "U1") (pin "2") (pinfunction "DO(IO1)_2") (pintype "bidirectional"))
      (node (ref "U2") (pin "27") (pinfunction "IO2_27") (pintype "bidirectional"))
    )
    (net (code "20") (name "MOSI") (class "Default")
      (node (ref "D11") (pin "2") (pinfunction "2_2") (pintype "passive"))
      (node (ref "J1") (pin "14") (pinfunction "14_14") (pintype "bidirectional"))
      (node (ref "J4") (pin "P3") (pinfunction "CMD_P3") (pintype "bidirectional"))
      (node (ref "R7") (pin "1") (pinfunction "1_1") (pintype "passive"))
      (node (ref "TP7") (pin "TP") (pinfunction "TP_TP") (pintype "input"))
      (node (ref "U1") (pin "5") (pinfunction "DI(IO0)_5") (pintype "bidirectional"))
      (node (ref "U2") (pin "7") (pinfunction "IO7_7") (pintype "bidirectional"))
    )
    (net (code "21") (name "Net-(CHG_LED-PadC)") (class "Default")
      (node (ref "CHG_LED") (pin "C") (pinfunction "C_C") (pintype "passive"))
      (node (ref "R1_BAT") (pin "1") (pinfunction "1_1") (pintype "passive"))
    )
    (net (code "22") (name "Net-(D2-CATHODE)") (class "Default")
      (node (ref "C1_BAT1") (pin "1") (pinfunction "1_1") (pintype "passive"))
      (node (ref "D2") (pin "1") (pinfunction "CATHODE_1") (pintype "bidirectional"))
      (node (ref "IC4") (pin "1") (pinfunction "VIN_1") (pintype "bidirectional"))
      (node (ref "IC4") (pin "3") (pinfunction "CE_3") (pintype "bidirectional"))
      (node (ref "Q1") (pin "2") (pinfunction "S_2") (pintype "bidirectional"))
    )
    (net (code "23") (name "Net-(D3-A)") (class "Default")
      (node (ref "C4") (pin "1") (pinfunction "1_1") (pintype "passive"))
      (node (ref "D3") (pin "1") (pinfunction "A_1") (pintype "bidirectional"))
      (node (ref "D4") (pin "2") (pinfunction "K_2") (pintype "bidirectional"))
    )
    (net (code "24") (name "Net-(D7-CATHODE)") (class "Default")
      (node (ref "D7") (pin "1") (pinfunction "CATHODE_1") (pintype "bidirectional"))
      (node (ref "R_CAPACITOR") (pin "1") (pinfunction "1_1") (pintype "passive"))
    )
    (net (code "25") (name "Net-(EPD_C1-Pad2)") (class "Default")
      (node (ref "EPD_C1") (pin "2") (pinfunction "2_2") (pintype "passive"))
      (node (ref "J1") (pin "4") (pinfunction "4_4") (pintype "bidirectional"))
    )
    (net (code "26") (name "Net-(EPD_C2-Pad2)") (class "Default")
      (node (ref "EPD_C2") (pin "2") (pinfunction "2_2") (pintype "passive"))
      (node (ref "J1") (pin "5") (pinfunction "5_5") (pintype "bidirectional"))
    )
    (net (code "27") (name "Net-(EPD_C6-Pad2)") (class "Default")
      (node (ref "EPD_C6") (pin "2") (pinfunction "2_2") (pintype "passive"))
      (node (ref "J1") (pin "18") (pinfunction "18_18") (pintype "bidirectional"))
    )
    (net (code "28") (name "Net-(EPD_C7-Pad2)") (class "Default")
      (node (ref "EPD_C7") (pin "2") (pinfunction "2_2") (pintype "passive"))
      (node (ref "J1") (pin "19") (pinfunction "19_19") (pintype "bidirectional"))
    )
    (net (code "29") (name "Net-(EPD_C8-Pad2)") (class "Default")
      (node (ref "EPD_C8") (pin "2") (pinfunction "2_2") (pintype "passive"))
      (node (ref "J1") (pin "20") (pinfunction "20_20") (pintype "bidirectional"))
    )
    (net (code "30") (name "Net-(EPD_C10-Pad2)") (class "Default")
      (node (ref "EPD_C10") (pin "2") (pinfunction "2_2") (pintype "passive"))
      (node (ref "J1") (pin "22") (pinfunction "22_22") (pintype "bidirectional"))
    )
    (net (code "31") (name "Net-(EPD_C12-Pad2)") (class "Default")
      (node (ref "EPD_C12") (pin "2") (pinfunction "2_2") (pintype "passive"))
      (node (ref "J1") (pin "24") (pinfunction "24_24") (pintype "bidirectional"))
    )
    (net (code "32") (name "Net-(IC1-CT)") (class "Default")
      (node (ref "C_DELAY") (pin "1") (pinfunction "1_1") (pintype "passive"))
      (node (ref "IC1") (pin "5") (pinfunction "CT_5") (pintype "bidirectional"))
    )
    (net (code "33") (name "Net-(J2-PadA5)") (class "Default")
      (node (ref "J2") (pin "A5") (pinfunction "A5_A5") (pintype "bidirectional"))
      (node (ref "R2-USB1") (pin "2") (pinfunction "2_2") (pintype "passive"))
    )
    (net (code "34") (name "Net-(J2-PadB5)") (class "Default")
      (node (ref "J2") (pin "B5") (pinfunction "B5_B5") (pintype "bidirectional"))
      (node (ref "R2-USB") (pin "1") (pinfunction "1_1") (pintype "passive"))
    )
    (net (code "35") (name "Net-(MCP73831-PROG)") (class "Default")
      (node (ref "MCP73831") (pin "5") (pinfunction "PROG_5") (pintype "input"))
      (node (ref "R2_BAT") (pin "2") (pinfunction "2_2") (pintype "passive"))
    )
    (net (code "36") (name "Net-(MCP73831-STAT)") (class "Default")
      (node (ref "MCP73831") (pin "1") (pinfunction "STAT_1") (pintype "output"))
      (node (ref "R1_BAT") (pin "2") (pinfunction "2_2") (pintype "passive"))
    )
    (net (code "37") (name "PREVGH") (class "Default")
      (node (ref "D5") (pin "2") (pinfunction "K_2") (pintype "bidirectional"))
      (node (ref "EPD_C9") (pin "2") (pinfunction "2_2") (pintype "passive"))
      (node (ref "J1") (pin "21") (pinfunction "21_21") (pintype "bidirectional"))
    )
    (net (code "38") (name "PREVGL") (class "Default")
      (node (ref "D4") (pin "1") (pinfunction "A_1") (pintype "bidirectional"))
      (node (ref "EPD_C11") (pin "2") (pinfunction "2_2") (pintype "passive"))
      (node (ref "J1") (pin "23") (pinfunction "23_23") (pintype "bidirectional"))
    )
    (net (code "39") (name "RESE") (class "Default")
      (node (ref "J1") (pin "3") (pinfunction "3_3") (pintype "bidirectional"))
      (node (ref "Q3") (pin "2") (pinfunction "S_2") (pintype "bidirectional"))
      (node (ref "R3") (pin "2") (pinfunction "2_2") (pintype "passive"))
    )
    (net (code "40") (name "RESE'") (class "Default")
      (node (ref "R2") (pin "2") (pinfunction "2_2") (pintype "passive"))
      (node (ref "R3") (pin "1") (pinfunction "1_1") (pintype "passive"))
      (node (ref "SJ1") (pin "2") (pinfunction "2_2") (pintype "passive"))
    )
    (net (code "41") (name "RESET") (class "Default")
      (node (ref "C5") (pin "1") (pinfunction "1_1") (pintype "passive"))
      (node (ref "IC1") (pin "1") (pinfunction "VOUT_1") (pintype "bidirectional"))
      (node (ref "RESET_BUTTON") (pin "3") (pinfunction "3_3") (pintype "passive"))
      (node (ref "RESET_BUTTON") (pin "4") (pinfunction "4_4") (pintype "passive"))
      (node (ref "R_RESET") (pin "1") (pinfunction "1_1") (pintype "passive"))
      (node (ref "U2") (pin "3") (pinfunction "EN_3") (pintype "input"))
    )
    (net (code "42") (name "RTC_RST") (class "Default")
      (node (ref "U2") (pin "16") (pinfunction "IO18_16") (pintype "bidirectional"))
      (node (ref "U3") (pin "4") (pinfunction "~{RST}_4") (pintype "input"))
    )
    (net (code "43") (name "RX") (class "Default")
      (node (ref "TP2") (pin "TP") (pinfunction "TP_TP") (pintype "input"))
      (node (ref "U2") (pin "24") (pinfunction "RXD0/GPIO17_24") (pintype "bidirectional"))
    )
    (net (code "44") (name "SCK") (class "Default")
      (node (ref "D10") (pin "2") (pinfunction "2_2") (pintype "passive"))
      (node (ref "J1") (pin "13") (pinfunction "13_13") (pintype "bidirectional"))
      (node (ref "J4") (pin "P5") (pinfunction "CLK_P5") (pintype "bidirectional"))
      (node (ref "R6") (pin "1") (pinfunction "1_1") (pintype "passive"))
      (node (ref "TP8") (pin "TP") (pinfunction "TP_TP") (pintype "input"))
      (node (ref "U1") (pin "6") (pinfunction "CLK_6") (pintype "input"))
      (node (ref "U2") (pin "6") (pinfunction "IO6_6") (pintype "bidirectional"))
    )
    (net (code "45") (name "SCL") (class "Default")
      (node (ref "J3") (pin "4") (pinfunction "4_4") (pintype "passive"))
      (node (ref "R2-PINH") (pin "1") (pinfunction "1_1") (pintype "passive"))
      (node (ref "SENSOR2") (pin "4") (pinfunction "SCK_4") (pintype "input"))
      (node (ref "U2") (pin "20") (pinfunction "IO22_20") (pintype "bidirectional"))
      (node (ref "U3") (pin "16") (pinfunction "SCL_16") (pintype "input"))
      (node (ref "U4") (pin "7") (pinfunction "SCL_7") (pintype "input"))
    )
    (net (code "46") (name "SDA") (class "Default")
      (node (ref "J3") (pin "3") (pinfunction "3_3") (pintype "passive"))
      (node (ref "R1-PINH") (pin "1") (pinfunction "1_1") (pintype "passive"))
      (node (ref "SENSOR2") (pin "3") (pinfunction "SDI_3") (pintype "bidirectional"))
      (node (ref "U2") (pin "19") (pinfunction "IO21_19") (pintype "bidirectional"))
      (node (ref "U3") (pin "15") (pinfunction "SDA_15") (pintype "bidirectional"))
      (node (ref "U4") (pin "8") (pinfunction "SDA_8") (pintype "bidirectional"))
    )
    (net (code "47") (name "SRC") (class "Default")
      (node (ref "C4") (pin "2") (pinfunction "2_2") (pintype "passive"))
      (node (ref "D5") (pin "1") (pinfunction "A_1") (pintype "bidirectional"))
      (node (ref "L1") (pin "1") (pinfunction "1_1") (pintype "passive"))
      (node (ref "Q3") (pin "3") (pinfunction "D_3") (pintype "bidirectional"))
    )
    (net (code "48") (name "SS_SD") (class "Default")
      (node (ref "D8") (pin "2") (pinfunction "2_2") (pintype "passive"))
      (node (ref "J4") (pin "P2") (pinfunction "CD/DAT3_P2") (pintype "bidirectional"))
      (node (ref "R10") (pin "1") (pinfunction "1_1") (pintype "passive"))
      (node (ref "U2") (pin "4") (pinfunction "IO4_4") (pintype "bidirectional"))
    )
    (net (code "49") (name "TX") (class "Default")
      (node (ref "TP1") (pin "TP") (pinfunction "TP_TP") (pintype "input"))
      (node (ref "U2") (pin "25") (pinfunction "TXD0/GPIO16_25") (pintype "bidirectional"))
    )
    (net (code "50") (name "USB_D+") (class "Default")
      (node (ref "D1") (pin "4") (pinfunction "I/O2_2_4") (pintype "bidirectional"))
      (node (ref "U2") (pin "14") (pinfunction "IO13_14") (pintype "bidirectional"))
    )
    (net (code "51") (name "USB_D-") (class "Default")
      (node (ref "D1") (pin "6") (pinfunction "I/O1_2_6") (pintype "bidirectional"))
      (node (ref "U2") (pin "13") (pinfunction "IO12_13") (pintype "bidirectional"))
    )
    (net (code "52") (name "VBAT") (class "Default")
      (node (ref "C2_BAT") (pin "1") (pinfunction "1_1") (pintype "passive"))
      (node (ref "MCP73831") (pin "3") (pinfunction "VBAT_3") (pintype "power_in"))
      (node (ref "Q1") (pin "3") (pinfunction "D_3") (pintype "bidirectional"))
      (node (ref "TP3") (pin "TP") (pinfunction "TP_TP") (pintype "input"))
      (node (ref "U4") (pin "2") (pinfunction "CELL_2") (pintype "power_in"))
      (node (ref "U4") (pin "3") (pinfunction "VDD_3") (pintype "power_in"))
    )
    (net (code "53") (name "VBUS") (class "Default")
      (node (ref "C1_BAT") (pin "1") (pinfunction "1_1") (pintype "passive"))
      (node (ref "C4_USB") (pin "1") (pinfunction "1_1") (pintype "passive"))
      (node (ref "C5_USB") (pin "1") (pinfunction "1_1") (pintype "passive"))
      (node (ref "CHG_LED") (pin "A") (pinfunction "A_A") (pintype "passive"))
      (node (ref "D1") (pin "2") (pinfunction "GND_2") (pintype "bidirectional"))
      (node (ref "D2") (pin "2") (pinfunction "ANODE_2") (pintype "bidirectional"))
      (node (ref "MCP73831") (pin "4") (pinfunction "VIN_4") (pintype "power_in"))
      (node (ref "PFMF.050.1") (pin "2") (pinfunction "2_2") (pintype "passive"))
      (node (ref "Q1") (pin "1") (pinfunction "G_1") (pintype "bidirectional"))
      (node (ref "R1_PWRUSB") (pin "2") (pinfunction "2_2") (pintype "passive"))
      (node (ref "TP14") (pin "TP") (pinfunction "TP_TP") (pintype "input"))
    )
    (net (code "54") (name "VRTC") (class "Default")
      (node (ref "C10_SUPERCAP") (pin "1") (pinfunction "1_1") (pintype "passive"))
      (node (ref "C8") (pin "1") (pinfunction "1_1") (pintype "passive"))
      (node (ref "R_CAPACITOR") (pin "2") (pinfunction "2_2") (pintype "passive"))
      (node (ref "U3") (pin "14") (pinfunction "VBAT_14") (pintype "power_in"))
    )
    (net (code "55") (name "VUSB") (class "Default")
      (node (ref "J2") (pin "A4") (pinfunction "A4_A4") (pintype "bidirectional"))
      (node (ref "J2") (pin "A9") (pinfunction "A9_A9") (pintype "bidirectional"))
      (node (ref "J2") (pin "B4") (pinfunction "B4_B4") (pintype "bidirectional"))
      (node (ref "J2") (pin "B9") (pinfunction "B9_B9") (pintype "bidirectional"))
      (node (ref "PFMF.050.1") (pin "1") (pinfunction "1_1") (pintype "passive"))
    )
    (net (code "56") (name "unconnected-(IC1-NC-Pad4)") (class "Default")
      (node (ref "IC1") (pin "4") (pinfunction "NC_4") (pintype "no_connect"))
    )
    (net (code "57") (name "unconnected-(IC4-NC-Pad4)") (class "Default")
      (node (ref "IC4") (pin "4") (pinfunction "NC_4") (pintype "no_connect"))
    )
    (net (code "58") (name "unconnected-(J1-Pad1)") (class "Default")
      (node (ref "J1") (pin "1") (pinfunction "1_1") (pintype "bidirectional"))
    )
    (net (code "59") (name "unconnected-(J1-Pad6)") (class "Default")
      (node (ref "J1") (pin "6") (pinfunction "6_6") (pintype "bidirectional"))
    )
    (net (code "60") (name "unconnected-(J1-Pad7)") (class "Default")
      (node (ref "J1") (pin "7") (pinfunction "7_7") (pintype "bidirectional"))
    )
    (net (code "61") (name "unconnected-(J2-PadA8)") (class "Default")
      (node (ref "J2") (pin "A8") (pinfunction "A8_A8") (pintype "bidirectional"))
    )
    (net (code "62") (name "unconnected-(J2-PadB8)") (class "Default")
      (node (ref "J2") (pin "B8") (pinfunction "B8_B8") (pintype "bidirectional"))
    )
    (net (code "63") (name "unconnected-(J4-DAT1-PadP8)") (class "Default")
      (node (ref "J4") (pin "P8") (pinfunction "DAT1_P8") (pintype "bidirectional"))
    )
    (net (code "64") (name "unconnected-(J4-DAT2-PadP1)") (class "Default")
      (node (ref "J4") (pin "P1") (pinfunction "DAT2_P1") (pintype "bidirectional"))
    )
    (net (code "65") (name "unconnected-(J4-DETECTION_1-PadS1)") (class "Default")
      (node (ref "J4") (pin "S1") (pinfunction "DETECTION_1_S1") (pintype "bidirectional"))
    )
    (net (code "66") (name "unconnected-(J4-DETECTION_2-PadS2)") (class "Default")
      (node (ref "J4") (pin "S2") (pinfunction "DETECTION_2_S2") (pintype "bidirectional"))
    )
    (net (code "67") (name "unconnected-(U2-NC-Pad22)") (class "Default")
      (node (ref "U2") (pin "22") (pinfunction "NC_22") (pintype "no_connect"))
    )
    (net (code "68") (name "unconnected-(U4-~{ALERT}-Pad5)") (class "Default")
      (node (ref "U4") (pin "5") (pinfunction "~{ALERT}_5") (pintype "output"))
    )
  )
)
